# BLE112_Breakout_Board_v1_1.net
KiCad netlist of a schematic drawn in EAGLE
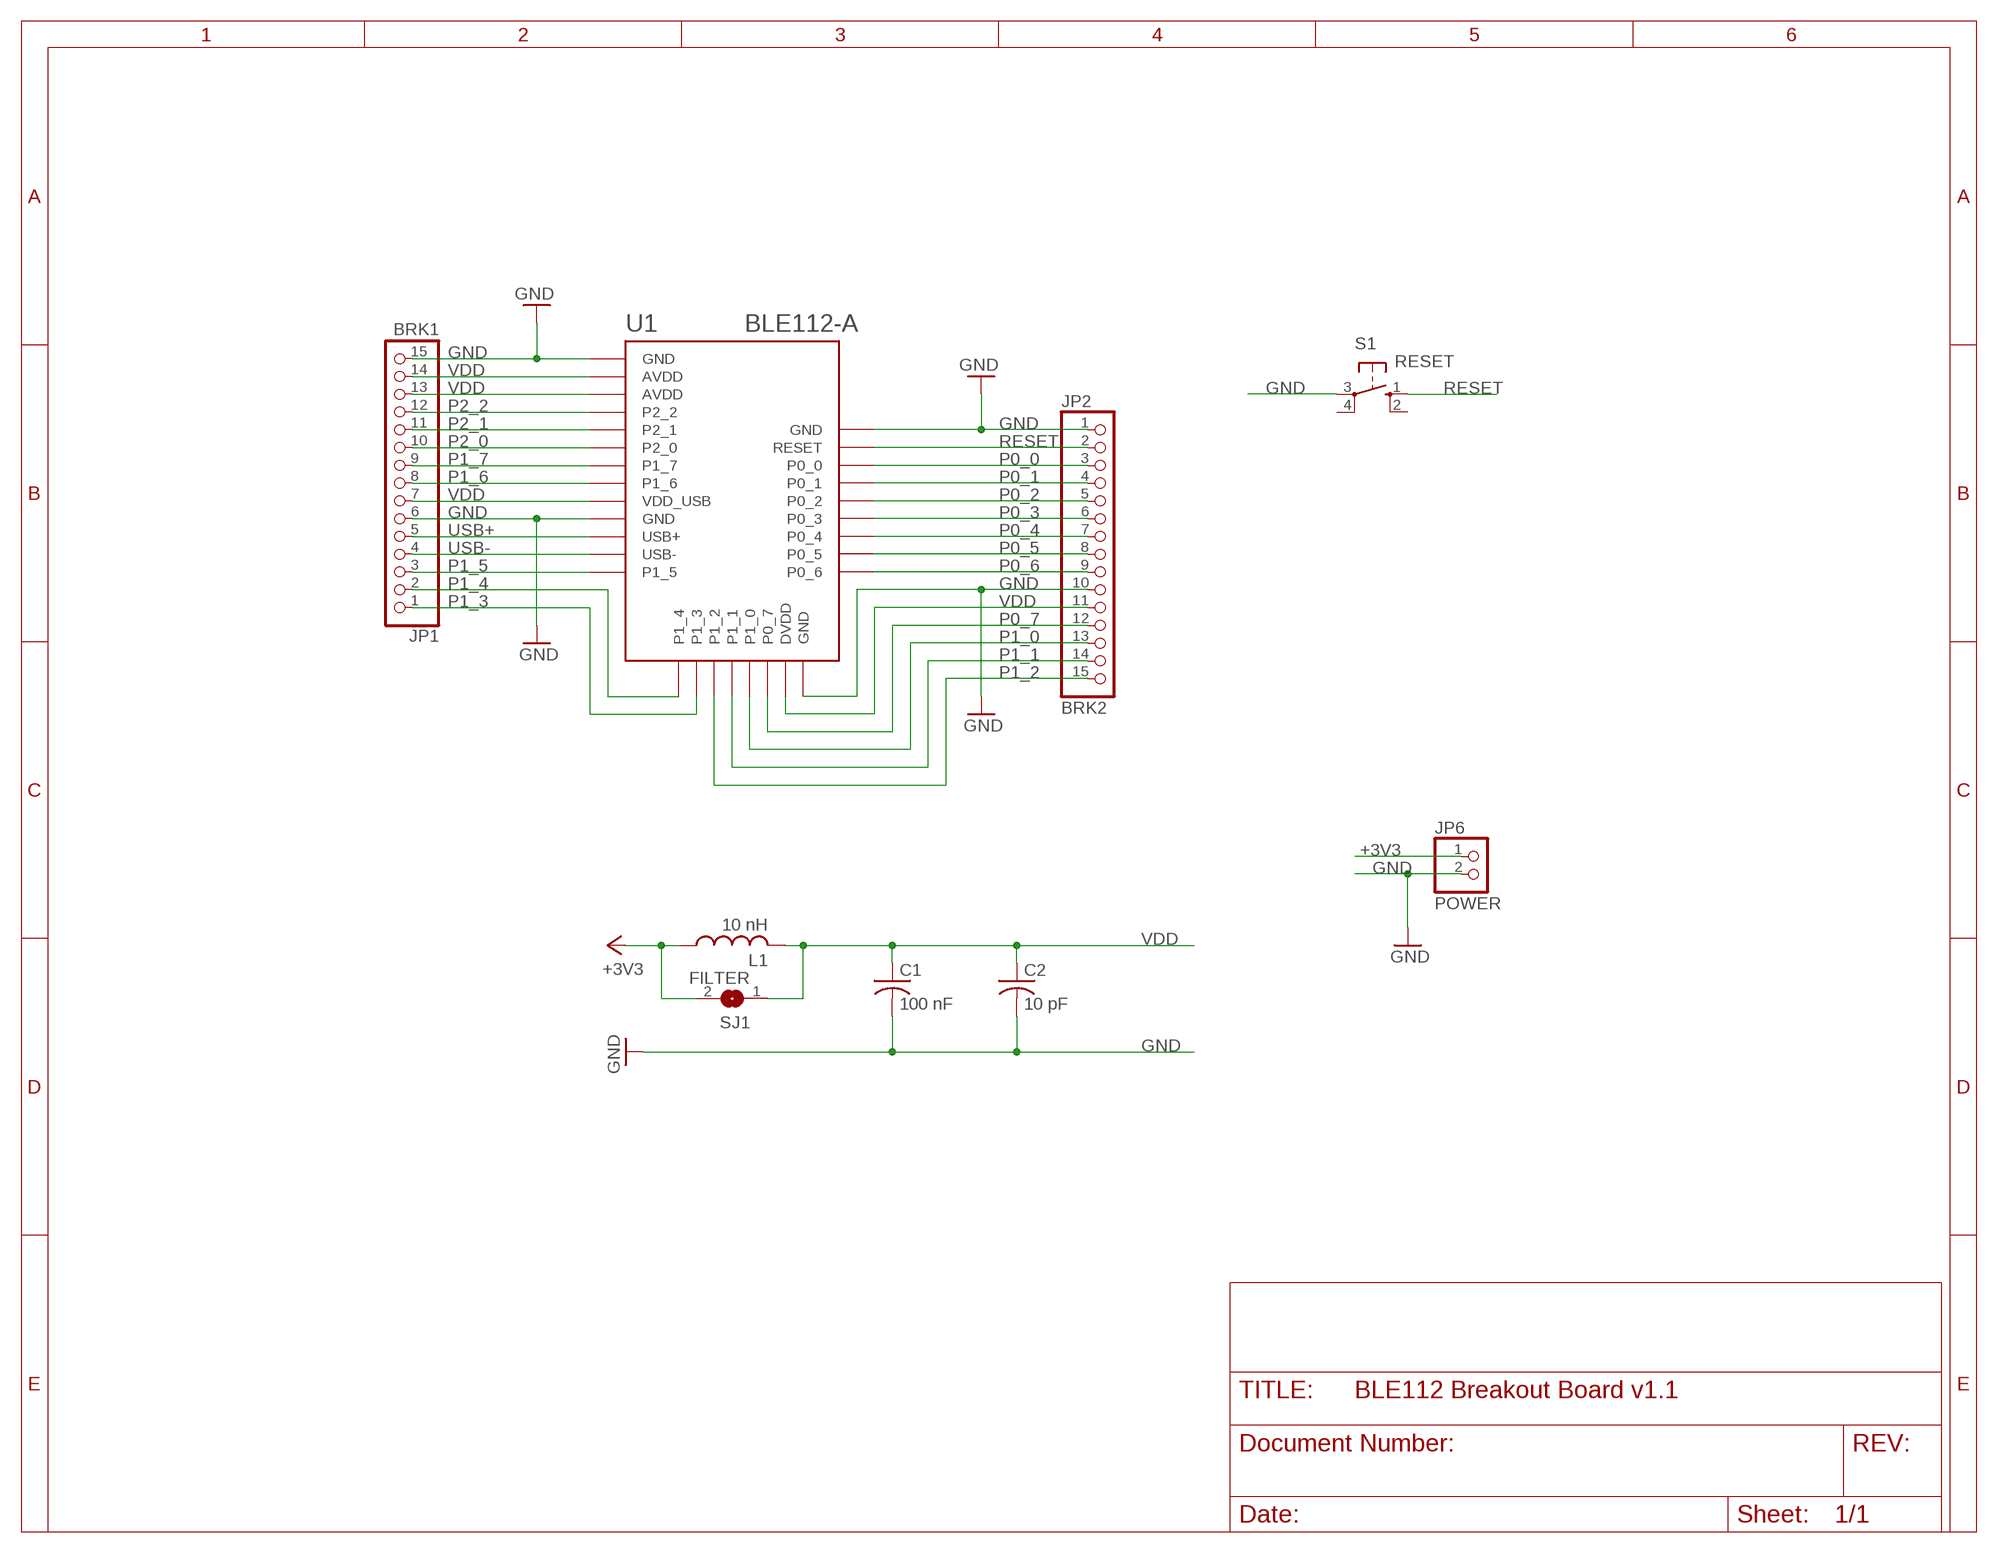
[diagram p0: schematic, sheet 1]

(export (version "E")
  (design (tool "Eeschema 10.0.6"))
  (components
    (comp (ref "C1")
      (value "100 nF")
      (footprint "eagle-import:C025-025X050")
      (libsource (lib "eagle-import") (part "C-US025-025X050"))
    )
    (comp (ref "C2")
      (value "10 pF")
      (footprint "eagle-import:C025-025X050")
      (libsource (lib "eagle-import") (part "C-US025-025X050"))
    )
    (comp (ref "JP1")
      (value "BRK1")
      (footprint "eagle-import:1X15")
      (libsource (lib "eagle-import") (part "PINHD-1X15"))
    )
    (comp (ref "JP2")
      (value "BRK2")
      (footprint "eagle-import:1X15")
      (libsource (lib "eagle-import") (part "PINHD-1X15"))
    )
    (comp (ref "JP6")
      (value "POWER")
      (footprint "eagle-import:1X02")
      (libsource (lib "eagle-import") (part "PINHD-1X2"))
    )
    (comp (ref "L1")
      (value "10 nH")
      (footprint "eagle-import:0204_7")
      (libsource (lib "eagle-import") (part "L-US0204/7"))
    )
    (comp (ref "S1")
      (value "RESET")
      (footprint "eagle-import:B3F-10XX")
      (fields (field (name "MPN") "B3F-1000"))
      (libsource (lib "eagle-import") (part "10-XX"))
    )
    (comp (ref "SJ1")
      (value "FILTER")
      (footprint "eagle-import:SJ")
      (libsource (lib "eagle-import") (part "SJ"))
    )
    (comp (ref "U1")
      (value "BLE112-A")
      (footprint "eagle-import:BLE112-A")
      (libsource (lib "eagle-import") (part "BLE112-A-VISUAL"))
    )
  )
  (nets
    (net (code "1") (name "+3V3") (class "Default")
      (node (ref "JP6") (pin "1") (pinfunction "1_1") (pintype "passive"))
      (node (ref "L1") (pin "1") (pinfunction "1_1") (pintype "passive"))
      (node (ref "SJ1") (pin "2") (pinfunction "2_2") (pintype "passive"))
    )
    (net (code "2") (name "/P0_0") (class "Default")
      (node (ref "JP2") (pin "3") (pinfunction "3_3") (pintype "passive"))
      (node (ref "U1") (pin "P0_0") (pinfunction "P0_0_P0_0") (pintype "bidirectional"))
    )
    (net (code "3") (name "/P0_1") (class "Default")
      (node (ref "JP2") (pin "4") (pinfunction "4_4") (pintype "passive"))
      (node (ref "U1") (pin "P0_1") (pinfunction "P0_1_P0_1") (pintype "bidirectional"))
    )
    (net (code "4") (name "/P0_2") (class "Default")
      (node (ref "JP2") (pin "5") (pinfunction "5_5") (pintype "passive"))
      (node (ref "U1") (pin "P0_2") (pinfunction "P0_2_P0_2") (pintype "bidirectional"))
    )
    (net (code "5") (name "/P0_3") (class "Default")
      (node (ref "JP2") (pin "6") (pinfunction "6_6") (pintype "passive"))
      (node (ref "U1") (pin "P0_3") (pinfunction "P0_3_P0_3") (pintype "bidirectional"))
    )
    (net (code "6") (name "/P0_4") (class "Default")
      (node (ref "JP2") (pin "7") (pinfunction "7_7") (pintype "passive"))
      (node (ref "U1") (pin "P0_4") (pinfunction "P0_4_P0_4") (pintype "bidirectional"))
    )
    (net (code "7") (name "/P0_5") (class "Default")
      (node (ref "JP2") (pin "8") (pinfunction "8_8") (pintype "passive"))
      (node (ref "U1") (pin "P0_5") (pinfunction "P0_5_P0_5") (pintype "bidirectional"))
    )
    (net (code "8") (name "/P0_6") (class "Default")
      (node (ref "JP2") (pin "9") (pinfunction "9_9") (pintype "passive"))
      (node (ref "U1") (pin "P0_6") (pinfunction "P0_6_P0_6") (pintype "bidirectional"))
    )
    (net (code "9") (name "/P0_7") (class "Default")
      (node (ref "JP2") (pin "12") (pinfunction "12_12") (pintype "passive"))
      (node (ref "U1") (pin "P0_7") (pinfunction "P0_7_P0_7") (pintype "bidirectional"))
    )
    (net (code "10") (name "/P1_0") (class "Default")
      (node (ref "JP2") (pin "13") (pinfunction "13_13") (pintype "passive"))
      (node (ref "U1") (pin "P1_0") (pinfunction "P1_0_P1_0") (pintype "bidirectional"))
    )
    (net (code "11") (name "/P1_1") (class "Default")
      (node (ref "JP2") (pin "14") (pinfunction "14_14") (pintype "passive"))
      (node (ref "U1") (pin "P1_1") (pinfunction "P1_1_P1_1") (pintype "bidirectional"))
    )
    (net (code "12") (name "/P1_2") (class "Default")
      (node (ref "JP2") (pin "15") (pinfunction "15_15") (pintype "passive"))
      (node (ref "U1") (pin "P1_2") (pinfunction "P1_2_P1_2") (pintype "bidirectional"))
    )
    (net (code "13") (name "/P1_3") (class "Default")
      (node (ref "JP1") (pin "1") (pinfunction "1_1") (pintype "passive"))
      (node (ref "U1") (pin "P1_3") (pinfunction "P1_3_P1_3") (pintype "bidirectional"))
    )
    (net (code "14") (name "/P1_4") (class "Default")
      (node (ref "JP1") (pin "2") (pinfunction "2_2") (pintype "passive"))
      (node (ref "U1") (pin "P1_4") (pinfunction "P1_4_P1_4") (pintype "bidirectional"))
    )
    (net (code "15") (name "/P1_5") (class "Default")
      (node (ref "JP1") (pin "3") (pinfunction "3_3") (pintype "passive"))
      (node (ref "U1") (pin "P1_5") (pinfunction "P1_5_P1_5") (pintype "bidirectional"))
    )
    (net (code "16") (name "/P1_6") (class "Default")
      (node (ref "JP1") (pin "8") (pinfunction "8_8") (pintype "passive"))
      (node (ref "U1") (pin "P1_6") (pinfunction "P1_6_P1_6") (pintype "bidirectional"))
    )
    (net (code "17") (name "/P1_7") (class "Default")
      (node (ref "JP1") (pin "9") (pinfunction "9_9") (pintype "passive"))
      (node (ref "U1") (pin "P1_7") (pinfunction "P1_7_P1_7") (pintype "bidirectional"))
    )
    (net (code "18") (name "/P2_0") (class "Default")
      (node (ref "JP1") (pin "10") (pinfunction "10_10") (pintype "passive"))
      (node (ref "U1") (pin "P2_0") (pinfunction "P2_0_P2_0") (pintype "bidirectional"))
    )
    (net (code "19") (name "/P2_1") (class "Default")
      (node (ref "JP1") (pin "11") (pinfunction "11_11") (pintype "passive"))
      (node (ref "U1") (pin "P2_1") (pinfunction "P2_1_P2_1") (pintype "bidirectional"))
    )
    (net (code "20") (name "/P2_2") (class "Default")
      (node (ref "JP1") (pin "12") (pinfunction "12_12") (pintype "passive"))
      (node (ref "U1") (pin "P2_2") (pinfunction "P2_2_P2_2") (pintype "bidirectional"))
    )
    (net (code "21") (name "/RESET") (class "Default")
      (node (ref "JP2") (pin "2") (pinfunction "2_2") (pintype "passive"))
      (node (ref "S1") (pin "1") (pinfunction "S_1") (pintype "passive"))
      (node (ref "U1") (pin "RESET") (pinfunction "RESET_RESET") (pintype "input"))
    )
    (net (code "22") (name "/USB+") (class "Default")
      (node (ref "JP1") (pin "5") (pinfunction "5_5") (pintype "passive"))
      (node (ref "U1") (pin "USB+") (pinfunction "USB+_USB+") (pintype "bidirectional"))
    )
    (net (code "23") (name "/USB-") (class "Default")
      (node (ref "JP1") (pin "4") (pinfunction "4_4") (pintype "passive"))
      (node (ref "U1") (pin "USB-") (pinfunction "USB-_USB-") (pintype "bidirectional"))
    )
    (net (code "24") (name "/VDD") (class "Default")
      (node (ref "C1") (pin "1") (pinfunction "1_1") (pintype "passive"))
      (node (ref "C2") (pin "1") (pinfunction "1_1") (pintype "passive"))
      (node (ref "JP1") (pin "13") (pinfunction "13_13") (pintype "passive"))
      (node (ref "JP1") (pin "14") (pinfunction "14_14") (pintype "passive"))
      (node (ref "JP1") (pin "7") (pinfunction "7_7") (pintype "passive"))
      (node (ref "JP2") (pin "11") (pinfunction "11_11") (pintype "passive"))
      (node (ref "L1") (pin "2") (pinfunction "2_2") (pintype "passive"))
      (node (ref "SJ1") (pin "1") (pinfunction "1_1") (pintype "passive"))
      (node (ref "U1") (pin "AVDD1") (pinfunction "AVDD_AVDD1") (pintype "power_in"))
      (node (ref "U1") (pin "AVDD2") (pinfunction "AVDD_AVDD2") (pintype "power_in"))
      (node (ref "U1") (pin "DVDD") (pinfunction "DVDD_DVDD") (pintype "power_in"))
      (node (ref "U1") (pin "VDD_USB") (pinfunction "VDD_USB_VDD_USB") (pintype "power_in"))
    )
    (net (code "25") (name "GND") (class "Default")
      (node (ref "C1") (pin "2") (pinfunction "2_2") (pintype "passive"))
      (node (ref "C2") (pin "2") (pinfunction "2_2") (pintype "passive"))
      (node (ref "JP1") (pin "15") (pinfunction "15_15") (pintype "passive"))
      (node (ref "JP1") (pin "6") (pinfunction "6_6") (pintype "passive"))
      (node (ref "JP2") (pin "1") (pinfunction "1_1") (pintype "passive"))
      (node (ref "JP2") (pin "10") (pinfunction "10_10") (pintype "passive"))
      (node (ref "JP6") (pin "2") (pinfunction "2_2") (pintype "passive"))
      (node (ref "S1") (pin "3") (pinfunction "P_3") (pintype "passive"))
      (node (ref "U1") (pin "GND1") (pinfunction "GND_GND1") (pintype "power_in"))
      (node (ref "U1") (pin "GND2") (pinfunction "GND_GND2") (pintype "power_in"))
      (node (ref "U1") (pin "GND3") (pinfunction "GND_GND3") (pintype "power_in"))
      (node (ref "U1") (pin "GND4") (pinfunction "GND_GND4") (pintype "power_in"))
    )
    (net (code "26") (name "unconnected-(S1-P1-Pad4)") (class "Default")
      (node (ref "S1") (pin "4") (pinfunction "P1_4") (pintype "passive"))
    )
    (net (code "27") (name "unconnected-(S1-S1-Pad2)") (class "Default")
      (node (ref "S1") (pin "2") (pinfunction "S1_2") (pintype "passive"))
    )
  )
)
